# blink1mk3_005t6_3535_4l_usbc.net
KiCad netlist of a schematic drawn in EAGLE
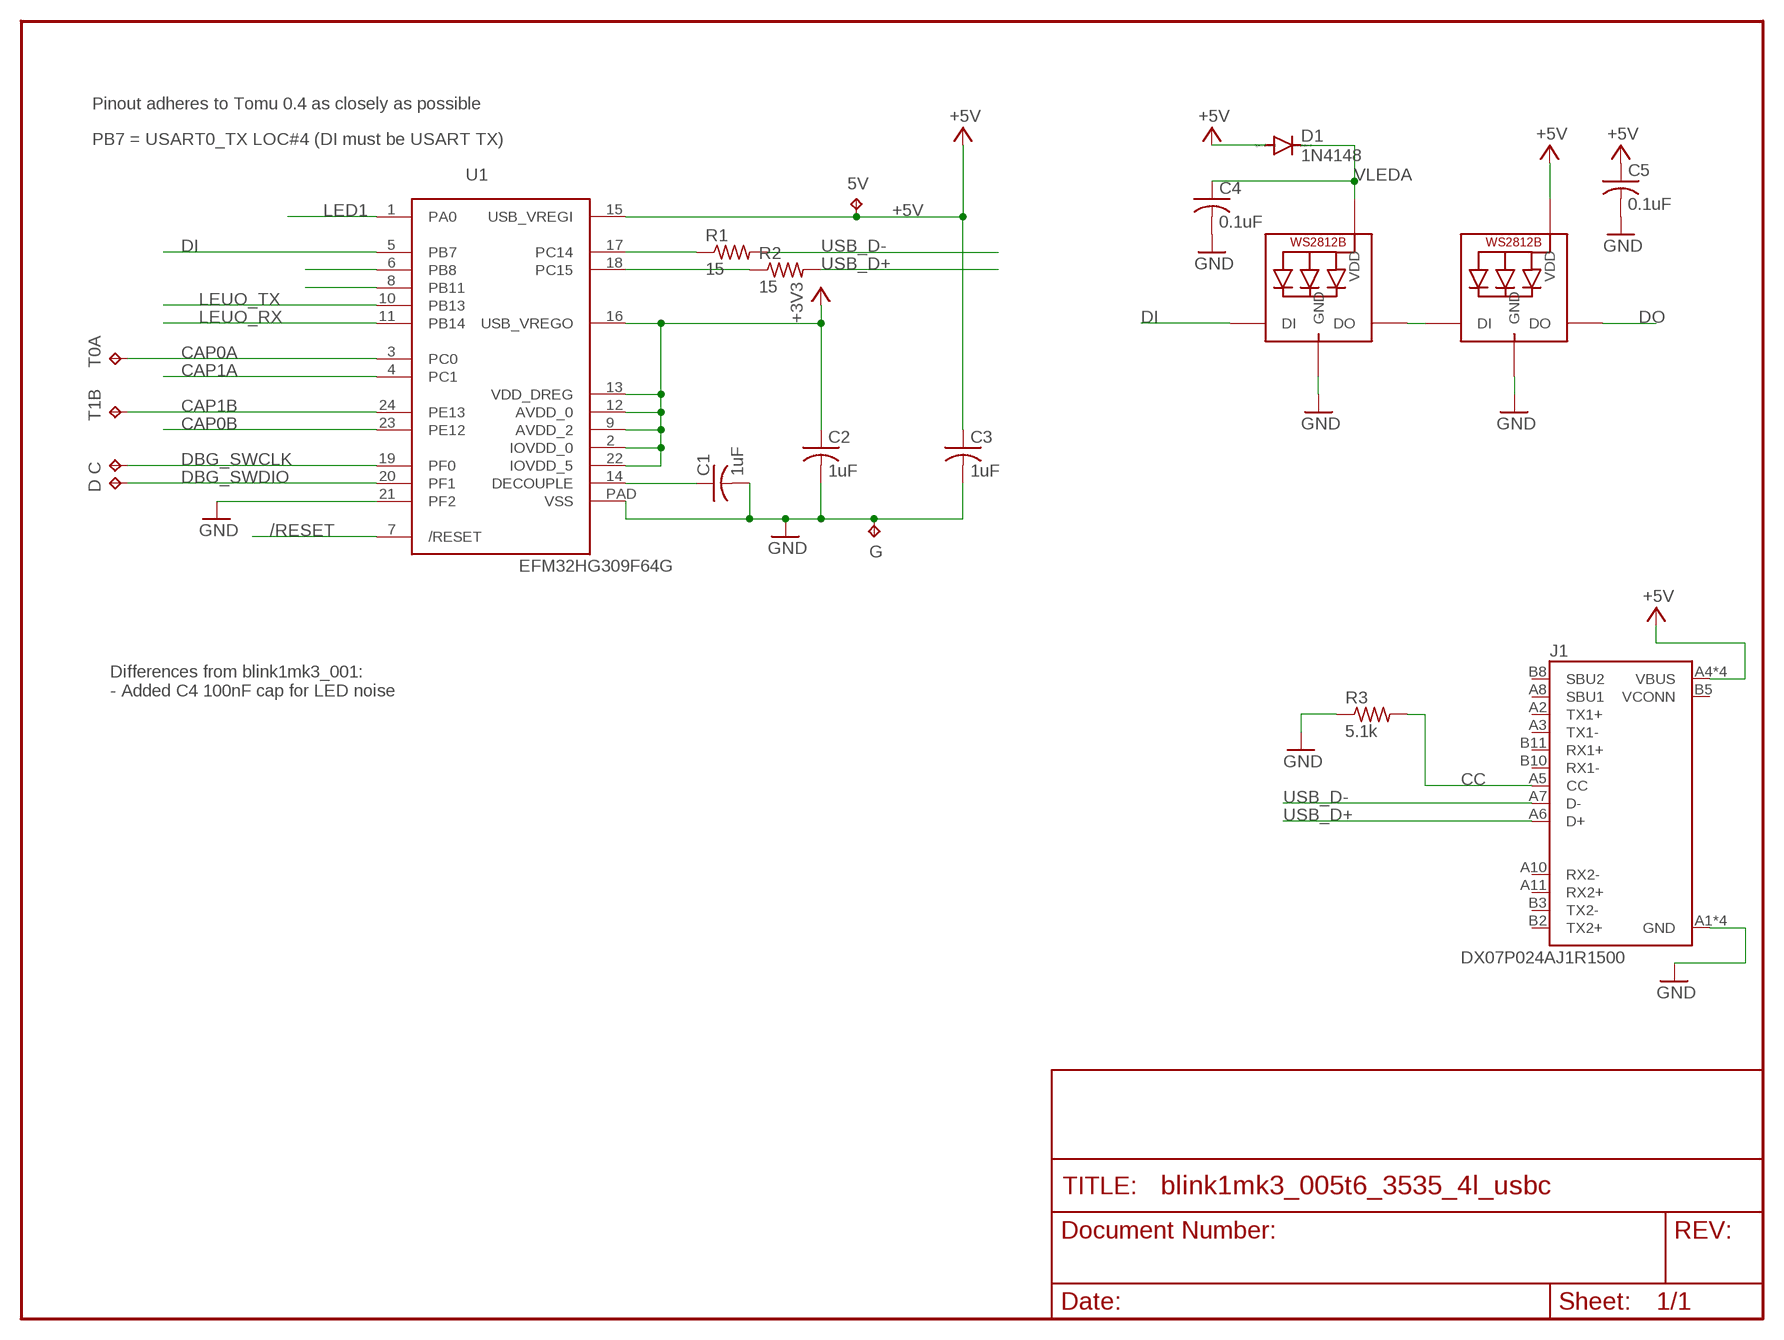
[diagram p0: schematic, sheet 1]

(export (version "E")
  (design (tool "Eeschema 10.0.6"))
  (components
    (comp (ref "5V")
      (value "TPTP10R")
      (footprint "eagle-import:TP10R")
      (libsource (lib "eagle-import") (part "TPTP10R"))
    )
    (comp (ref "C")
      (value "TPTP10R")
      (footprint "eagle-import:TP10R")
      (libsource (lib "eagle-import") (part "TPTP10R"))
    )
    (comp (ref "C1")
      (value "1uF")
      (footprint "eagle-import:C0402")
      (libsource (lib "eagle-import") (part "C-USC0402"))
    )
    (comp (ref "C2")
      (value "1uF")
      (footprint "eagle-import:C0402")
      (libsource (lib "eagle-import") (part "C-USC0402"))
    )
    (comp (ref "C3")
      (value "1uF")
      (footprint "eagle-import:C0402")
      (libsource (lib "eagle-import") (part "C-USC0402"))
    )
    (comp (ref "C4")
      (value "0.1uF")
      (footprint "eagle-import:C0402")
      (libsource (lib "eagle-import") (part "C-USC0402"))
    )
    (comp (ref "C5")
      (value "0.1uF")
      (footprint "eagle-import:C0402")
      (libsource (lib "eagle-import") (part "C-USC0402"))
    )
    (comp (ref "D")
      (value "TPTP10R")
      (footprint "eagle-import:TP10R")
      (libsource (lib "eagle-import") (part "TPTP10R"))
    )
    (comp (ref "D1")
      (value "1N4148")
      (footprint "eagle-import:SOD523")
      (libsource (lib "eagle-import") (part "DIODE-SOD523"))
    )
    (comp (ref "G")
      (value "TPTP10R")
      (footprint "eagle-import:TP10R")
      (libsource (lib "eagle-import") (part "TPTP10R"))
    )
    (comp (ref "J1")
      (value "DX07P024AJ1R1500")
      (footprint "eagle-import:JAE_DX07P024AJ1R1500")
      (fields (field (name "DIGI-KEY_PART_NUMBER") "670-2868-1-ND") (field (name "MF") "JAE Electronics"))
      (libsource (lib "eagle-import") (part "DX07P024AJ1R1500"))
    )
    (comp (ref "LED1")
      (value "WS2812B3535")
      (footprint "eagle-import:LED3535")
      (libsource (lib "eagle-import") (part "todstuff_1731349_WS2812B3535"))
    )
    (comp (ref "LED2")
      (value "SK6812MINI")
      (footprint "eagle-import:LED3535")
      (libsource (lib "eagle-import") (part "WS2812B3535"))
    )
    (comp (ref "R1")
      (value "15")
      (footprint "eagle-import:R0402")
      (libsource (lib "eagle-import") (part "R-US_R0402"))
    )
    (comp (ref "R2")
      (value "15")
      (footprint "eagle-import:R0402")
      (libsource (lib "eagle-import") (part "R-US_R0402"))
    )
    (comp (ref "R3")
      (value "5.1k")
      (footprint "eagle-import:R0402")
      (libsource (lib "eagle-import") (part "R-US_R0402"))
    )
    (comp (ref "T0A")
      (value "TPTP15R")
      (footprint "eagle-import:TP15R")
      (libsource (lib "eagle-import") (part "TPTP15R"))
    )
    (comp (ref "T1B")
      (value "TPTP15R")
      (footprint "eagle-import:TP15R")
      (libsource (lib "eagle-import") (part "TPTP15R"))
    )
    (comp (ref "U1")
      (value "EFM32HG309F64G")
      (footprint "eagle-import:QFN24PAD")
      (libsource (lib "eagle-import") (part "EFM32HG309F64G"))
    )
  )
  (nets
    (net (code "1") (name "+3V3") (class "Default")
      (node (ref "C2") (pin "1") (pinfunction "1_1") (pintype "passive"))
      (node (ref "U1") (pin "12") (pinfunction "AVDD_0_12") (pintype "bidirectional"))
      (node (ref "U1") (pin "13") (pinfunction "VDD_DREG_13") (pintype "bidirectional"))
      (node (ref "U1") (pin "16") (pinfunction "USB_VREGO_16") (pintype "bidirectional"))
      (node (ref "U1") (pin "2") (pinfunction "IOVDD_0_2") (pintype "bidirectional"))
      (node (ref "U1") (pin "22") (pinfunction "IOVDD_5_22") (pintype "bidirectional"))
      (node (ref "U1") (pin "9") (pinfunction "AVDD_2_9") (pintype "bidirectional"))
    )
    (net (code "2") (name "+5V") (class "Default")
      (node (ref "5V") (pin "TP") (pinfunction "TP_TP") (pintype "input"))
      (node (ref "C3") (pin "1") (pinfunction "1_1") (pintype "passive"))
      (node (ref "C5") (pin "1") (pinfunction "1_1") (pintype "passive"))
      (node (ref "D1") (pin "A") (pinfunction "A_A") (pintype "passive"))
      (node (ref "J1") (pin "A4") (pinfunction "VBUS_A4") (pintype "power_in"))
      (node (ref "J1") (pin "A9") (pinfunction "VBUS_A9") (pintype "power_in"))
      (node (ref "J1") (pin "B4") (pinfunction "VBUS_B4") (pintype "power_in"))
      (node (ref "J1") (pin "B9") (pinfunction "VBUS_B9") (pintype "power_in"))
      (node (ref "LED2") (pin "2") (pinfunction "VDD_2") (pintype "power_in"))
      (node (ref "U1") (pin "15") (pinfunction "USB_VREGI_15") (pintype "bidirectional"))
    )
    (net (code "3") (name "/CAP0A") (class "Default")
      (node (ref "T0A") (pin "TP") (pinfunction "TP_TP") (pintype "input"))
      (node (ref "U1") (pin "3") (pinfunction "PC0_3") (pintype "bidirectional"))
    )
    (net (code "4") (name "/CAP0B") (class "Default")
      (node (ref "U1") (pin "23") (pinfunction "PE12_23") (pintype "bidirectional"))
    )
    (net (code "5") (name "/CAP1A") (class "Default")
      (node (ref "U1") (pin "4") (pinfunction "PC1_4") (pintype "bidirectional"))
    )
    (net (code "6") (name "/CAP1B") (class "Default")
      (node (ref "T1B") (pin "TP") (pinfunction "TP_TP") (pintype "input"))
      (node (ref "U1") (pin "24") (pinfunction "PE13_24") (pintype "bidirectional"))
    )
    (net (code "7") (name "/CC") (class "Default")
      (node (ref "J1") (pin "A5") (pinfunction "CC_A5") (pintype "bidirectional"))
      (node (ref "R3") (pin "2") (pinfunction "2_2") (pintype "passive"))
    )
    (net (code "8") (name "/DBG_SWCLK") (class "Default")
      (node (ref "C") (pin "TP") (pinfunction "TP_TP") (pintype "input"))
      (node (ref "U1") (pin "19") (pinfunction "PF0_19") (pintype "bidirectional"))
    )
    (net (code "9") (name "/DBG_SWDIO") (class "Default")
      (node (ref "D") (pin "TP") (pinfunction "TP_TP") (pintype "input"))
      (node (ref "U1") (pin "20") (pinfunction "PF1_20") (pintype "bidirectional"))
    )
    (net (code "10") (name "/DI") (class "Default")
      (node (ref "LED1") (pin "1") (pinfunction "DI_1") (pintype "input"))
      (node (ref "U1") (pin "5") (pinfunction "PB7_5") (pintype "bidirectional"))
    )
    (net (code "11") (name "/DO") (class "Default")
      (node (ref "LED2") (pin "3") (pinfunction "DO_3") (pintype "output"))
    )
    (net (code "12") (name "/LED1") (class "Default")
      (node (ref "U1") (pin "1") (pinfunction "PA0_1") (pintype "bidirectional"))
    )
    (net (code "13") (name "/LEUO_RX") (class "Default")
      (node (ref "U1") (pin "11") (pinfunction "PB14_11") (pintype "bidirectional"))
    )
    (net (code "14") (name "/LEUO_TX") (class "Default")
      (node (ref "U1") (pin "10") (pinfunction "PB13_10") (pintype "bidirectional"))
    )
    (net (code "15") (name "/USB_D+") (class "Default")
      (node (ref "J1") (pin "A6") (pinfunction "D+_A6") (pintype "bidirectional"))
      (node (ref "R2") (pin "2") (pinfunction "2_2") (pintype "passive"))
    )
    (net (code "16") (name "/USB_D-") (class "Default")
      (node (ref "J1") (pin "A7") (pinfunction "D-_A7") (pintype "bidirectional"))
      (node (ref "R1") (pin "2") (pinfunction "2_2") (pintype "passive"))
    )
    (net (code "17") (name "/VCONN") (class "Default")
      (node (ref "J1") (pin "B5") (pinfunction "VCONN_B5") (pintype "power_in"))
    )
    (net (code "18") (name "/VLEDA") (class "Default")
      (node (ref "C4") (pin "1") (pinfunction "1_1") (pintype "passive"))
      (node (ref "D1") (pin "C") (pinfunction "C_C") (pintype "passive"))
      (node (ref "LED1") (pin "2") (pinfunction "VDD_2") (pintype "power_in"))
    )
    (net (code "19") (name "/{slash}RESET") (class "Default")
      (node (ref "U1") (pin "7") (pinfunction "/RESET_7") (pintype "bidirectional"))
    )
    (net (code "20") (name "GND") (class "Default")
      (node (ref "C1") (pin "2") (pinfunction "2_2") (pintype "passive"))
      (node (ref "C2") (pin "2") (pinfunction "2_2") (pintype "passive"))
      (node (ref "C3") (pin "2") (pinfunction "2_2") (pintype "passive"))
      (node (ref "C4") (pin "2") (pinfunction "2_2") (pintype "passive"))
      (node (ref "C5") (pin "2") (pinfunction "2_2") (pintype "passive"))
      (node (ref "G") (pin "TP") (pinfunction "TP_TP") (pintype "input"))
      (node (ref "J1") (pin "A1") (pinfunction "GND_A1") (pintype "power_in"))
      (node (ref "J1") (pin "A12") (pinfunction "GND_A12") (pintype "power_in"))
      (node (ref "J1") (pin "B1") (pinfunction "GND_B1") (pintype "power_in"))
      (node (ref "J1") (pin "B12") (pinfunction "GND_B12") (pintype "power_in"))
      (node (ref "LED1") (pin "4") (pinfunction "GND_4") (pintype "power_in"))
      (node (ref "LED2") (pin "4") (pinfunction "GND_4") (pintype "power_in"))
      (node (ref "R3") (pin "1") (pinfunction "1_1") (pintype "passive"))
      (node (ref "U1") (pin "21") (pinfunction "PF2_21") (pintype "bidirectional"))
      (node (ref "U1") (pin "PAD") (pinfunction "VSS_PAD") (pintype "bidirectional"))
    )
    (net (code "21") (name "Net-(LED1-DO)") (class "Default")
      (node (ref "LED1") (pin "3") (pinfunction "DO_3") (pintype "output"))
      (node (ref "LED2") (pin "1") (pinfunction "DI_1") (pintype "input"))
    )
    (net (code "22") (name "Net-(U1-DECOUPLE)") (class "Default")
      (node (ref "C1") (pin "1") (pinfunction "1_1") (pintype "passive"))
      (node (ref "U1") (pin "14") (pinfunction "DECOUPLE_14") (pintype "bidirectional"))
    )
    (net (code "23") (name "Net-(U1-PC14)") (class "Default")
      (node (ref "R1") (pin "1") (pinfunction "1_1") (pintype "passive"))
      (node (ref "U1") (pin "17") (pinfunction "PC14_17") (pintype "bidirectional"))
    )
    (net (code "24") (name "Net-(U1-PC15)") (class "Default")
      (node (ref "R2") (pin "1") (pinfunction "1_1") (pintype "passive"))
      (node (ref "U1") (pin "18") (pinfunction "PC15_18") (pintype "bidirectional"))
    )
    (net (code "25") (name "unconnected-(J1-RX1+-PadB11)") (class "Default")
      (node (ref "J1") (pin "B11") (pinfunction "RX1+_B11") (pintype "bidirectional"))
    )
    (net (code "26") (name "unconnected-(J1-RX1--PadB10)") (class "Default")
      (node (ref "J1") (pin "B10") (pinfunction "RX1-_B10") (pintype "bidirectional"))
    )
    (net (code "27") (name "unconnected-(J1-RX2+-PadA11)") (class "Default")
      (node (ref "J1") (pin "A11") (pinfunction "RX2+_A11") (pintype "bidirectional"))
    )
    (net (code "28") (name "unconnected-(J1-RX2--PadA10)") (class "Default")
      (node (ref "J1") (pin "A10") (pinfunction "RX2-_A10") (pintype "bidirectional"))
    )
    (net (code "29") (name "unconnected-(J1-SBU1-PadA8)") (class "Default")
      (node (ref "J1") (pin "A8") (pinfunction "SBU1_A8") (pintype "bidirectional"))
    )
    (net (code "30") (name "unconnected-(J1-SBU2-PadB8)") (class "Default")
      (node (ref "J1") (pin "B8") (pinfunction "SBU2_B8") (pintype "bidirectional"))
    )
    (net (code "31") (name "unconnected-(J1-TX1+-PadA2)") (class "Default")
      (node (ref "J1") (pin "A2") (pinfunction "TX1+_A2") (pintype "bidirectional"))
    )
    (net (code "32") (name "unconnected-(J1-TX1--PadA3)") (class "Default")
      (node (ref "J1") (pin "A3") (pinfunction "TX1-_A3") (pintype "bidirectional"))
    )
    (net (code "33") (name "unconnected-(J1-TX2+-PadB2)") (class "Default")
      (node (ref "J1") (pin "B2") (pinfunction "TX2+_B2") (pintype "bidirectional"))
    )
    (net (code "34") (name "unconnected-(J1-TX2--PadB3)") (class "Default")
      (node (ref "J1") (pin "B3") (pinfunction "TX2-_B3") (pintype "bidirectional"))
    )
    (net (code "35") (name "unconnected-(U1-PB8-Pad6)") (class "Default")
      (node (ref "U1") (pin "6") (pinfunction "PB8_6") (pintype "bidirectional"))
    )
    (net (code "36") (name "unconnected-(U1-PB11-Pad8)") (class "Default")
      (node (ref "U1") (pin "8") (pinfunction "PB11_8") (pintype "bidirectional"))
    )
  )
)
